# tek611r2.net
KiCad netlist of a schematic drawn in EAGLE
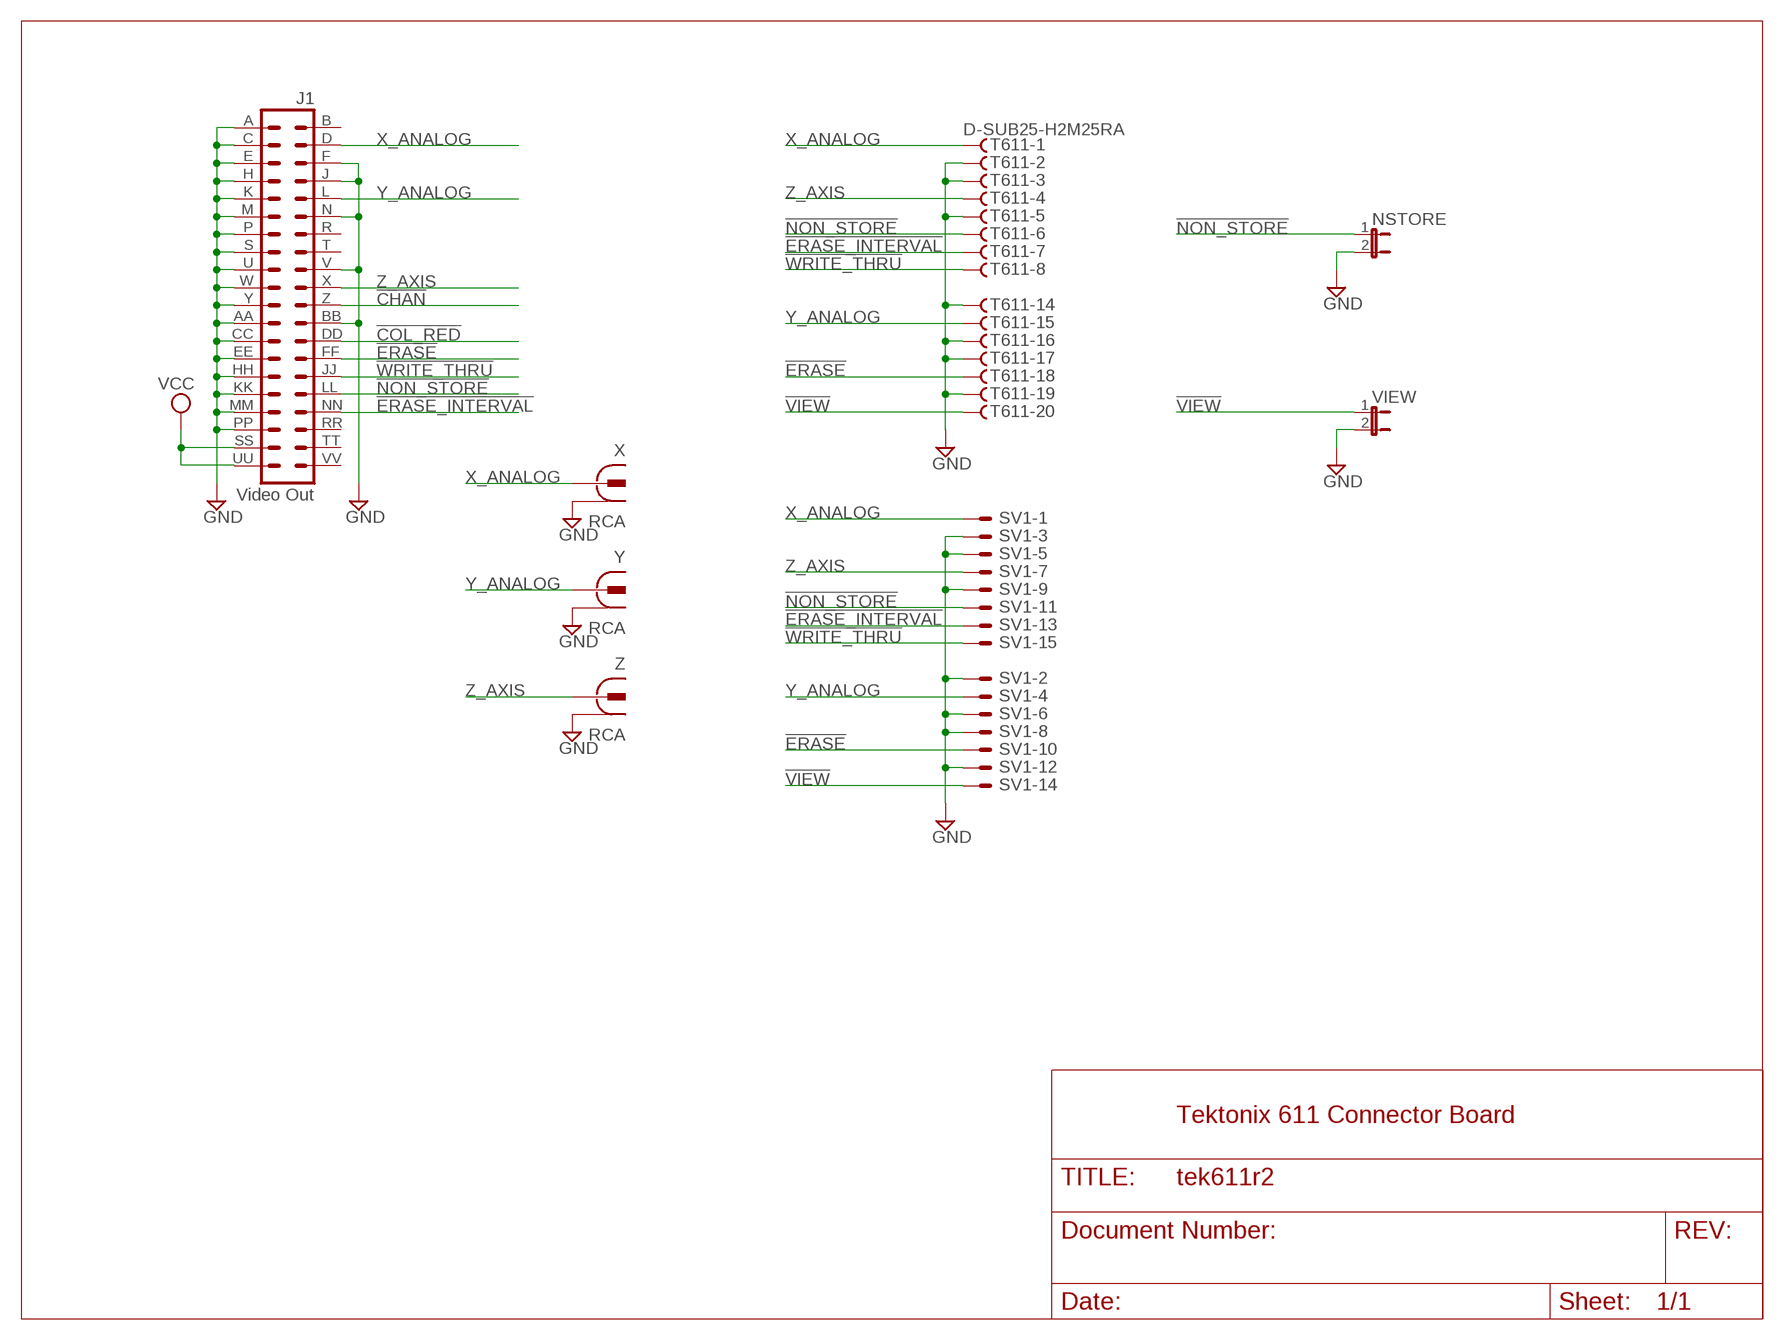
[diagram p0: schematic, sheet 1]

(export (version "E")
  (design (tool "Eeschema 10.0.6"))
  (components
    (comp (ref "J1")
      (value "Video Out")
      (footprint "eagle-import:DEC40PINH")
      (libsource (lib "eagle-import") (part "DEC40PINH"))
    )
    (comp (ref "NSTORE")
      (value "JP1E")
      (footprint "eagle-import:JP1")
      (libsource (lib "eagle-import") (part "JP1E"))
    )
    (comp (ref "SV1")
      (value "ML26LE")
      (footprint "eagle-import:ML26L")
      (libsource (lib "eagle-import") (part "ML26LE"))
    )
    (comp (ref "T611")
      (value "D-SUB25-H2M25RA")
      (footprint "eagle-import:H2M25RA")
      (libsource (lib "eagle-import") (part "D-SUB25-H2M25RA"))
    )
    (comp (ref "VIEW")
      (value "JP1E")
      (footprint "eagle-import:JP1")
      (libsource (lib "eagle-import") (part "JP1E"))
    )
    (comp (ref "X")
      (value "RCA")
      (footprint "eagle-import:RCA")
      (libsource (lib "eagle-import") (part "RCA"))
    )
    (comp (ref "Y")
      (value "RCA")
      (footprint "eagle-import:RCA")
      (libsource (lib "eagle-import") (part "RCA"))
    )
    (comp (ref "Z")
      (value "RCA")
      (footprint "eagle-import:RCA")
      (libsource (lib "eagle-import") (part "RCA"))
    )
  )
  (nets
    (net (code "1") (name "/X_ANALOG") (class "Default")
      (node (ref "J1") (pin "D") (pinfunction "4_D") (pintype "bidirectional"))
      (node (ref "SV1") (pin "1") (pinfunction "S_1") (pintype "passive"))
      (node (ref "T611") (pin "1") (pinfunction "F_1") (pintype "passive"))
      (node (ref "X") (pin "2") (pinfunction "2_2") (pintype "passive"))
    )
    (net (code "2") (name "/Y_ANALOG") (class "Default")
      (node (ref "J1") (pin "L") (pinfunction "10_L") (pintype "bidirectional"))
      (node (ref "SV1") (pin "4") (pinfunction "S_4") (pintype "passive"))
      (node (ref "T611") (pin "15") (pinfunction "F_15") (pintype "passive"))
      (node (ref "Y") (pin "2") (pinfunction "2_2") (pintype "passive"))
    )
    (net (code "3") (name "/Z_AXIS") (class "Default")
      (node (ref "J1") (pin "X") (pinfunction "20_X") (pintype "bidirectional"))
      (node (ref "SV1") (pin "7") (pinfunction "S_7") (pintype "passive"))
      (node (ref "T611") (pin "4") (pinfunction "F_4") (pintype "passive"))
      (node (ref "Z") (pin "2") (pinfunction "2_2") (pintype "passive"))
    )
    (net (code "4") (name "/~{CHAN}") (class "Default")
      (node (ref "J1") (pin "Z") (pinfunction "22_Z") (pintype "bidirectional"))
    )
    (net (code "5") (name "/~{COL_RED}") (class "Default")
      (node (ref "J1") (pin "DD") (pinfunction "26_DD") (pintype "bidirectional"))
    )
    (net (code "6") (name "/~{ERASE_INTERVAL}") (class "Default")
      (node (ref "J1") (pin "NN") (pinfunction "34_NN") (pintype "bidirectional"))
      (node (ref "SV1") (pin "13") (pinfunction "S_13") (pintype "passive"))
      (node (ref "T611") (pin "7") (pinfunction "F_7") (pintype "passive"))
    )
    (net (code "7") (name "/~{ERASE}") (class "Default")
      (node (ref "J1") (pin "FF") (pinfunction "28_FF") (pintype "bidirectional"))
      (node (ref "SV1") (pin "10") (pinfunction "S_10") (pintype "passive"))
      (node (ref "T611") (pin "18") (pinfunction "F_18") (pintype "passive"))
    )
    (net (code "8") (name "/~{NON_STORE}") (class "Default")
      (node (ref "J1") (pin "LL") (pinfunction "32_LL") (pintype "bidirectional"))
      (node (ref "NSTORE") (pin "1") (pinfunction "1_1") (pintype "passive"))
      (node (ref "SV1") (pin "11") (pinfunction "S_11") (pintype "passive"))
      (node (ref "T611") (pin "6") (pinfunction "F_6") (pintype "passive"))
    )
    (net (code "9") (name "/~{VIEW}") (class "Default")
      (node (ref "SV1") (pin "14") (pinfunction "S_14") (pintype "passive"))
      (node (ref "T611") (pin "20") (pinfunction "F_20") (pintype "passive"))
      (node (ref "VIEW") (pin "1") (pinfunction "1_1") (pintype "passive"))
    )
    (net (code "10") (name "/~{WRITE_THRU}") (class "Default")
      (node (ref "J1") (pin "JJ") (pinfunction "30_JJ") (pintype "bidirectional"))
      (node (ref "SV1") (pin "15") (pinfunction "S_15") (pintype "passive"))
      (node (ref "T611") (pin "8") (pinfunction "F_8") (pintype "passive"))
    )
    (net (code "11") (name "GND") (class "Default")
      (node (ref "J1") (pin "A") (pinfunction "1_A") (pintype "bidirectional"))
      (node (ref "J1") (pin "AA") (pinfunction "23_AA") (pintype "bidirectional"))
      (node (ref "J1") (pin "BB") (pinfunction "24_BB") (pintype "bidirectional"))
      (node (ref "J1") (pin "C") (pinfunction "3_C") (pintype "bidirectional"))
      (node (ref "J1") (pin "CC") (pinfunction "25_CC") (pintype "bidirectional"))
      (node (ref "J1") (pin "E") (pinfunction "5_E") (pintype "bidirectional"))
      (node (ref "J1") (pin "EE") (pinfunction "27_EE") (pintype "bidirectional"))
      (node (ref "J1") (pin "F") (pinfunction "6_F") (pintype "bidirectional"))
      (node (ref "J1") (pin "H") (pinfunction "7_H") (pintype "bidirectional"))
      (node (ref "J1") (pin "HH") (pinfunction "29_HH") (pintype "bidirectional"))
      (node (ref "J1") (pin "J") (pinfunction "8_J") (pintype "bidirectional"))
      (node (ref "J1") (pin "K") (pinfunction "9_K") (pintype "bidirectional"))
      (node (ref "J1") (pin "KK") (pinfunction "31_KK") (pintype "bidirectional"))
      (node (ref "J1") (pin "M") (pinfunction "11_M") (pintype "bidirectional"))
      (node (ref "J1") (pin "MM") (pinfunction "33_MM") (pintype "bidirectional"))
      (node (ref "J1") (pin "N") (pinfunction "12_N") (pintype "bidirectional"))
      (node (ref "J1") (pin "P") (pinfunction "13_P") (pintype "bidirectional"))
      (node (ref "J1") (pin "PP") (pinfunction "35_PP") (pintype "bidirectional"))
      (node (ref "J1") (pin "S") (pinfunction "15_S") (pintype "bidirectional"))
      (node (ref "J1") (pin "U") (pinfunction "17_U") (pintype "bidirectional"))
      (node (ref "J1") (pin "V") (pinfunction "18_V") (pintype "bidirectional"))
      (node (ref "J1") (pin "W") (pinfunction "19_W") (pintype "bidirectional"))
      (node (ref "J1") (pin "Y") (pinfunction "21_Y") (pintype "bidirectional"))
      (node (ref "NSTORE") (pin "2") (pinfunction "2_2") (pintype "passive"))
      (node (ref "SV1") (pin "12") (pinfunction "S_12") (pintype "passive"))
      (node (ref "SV1") (pin "2") (pinfunction "S_2") (pintype "passive"))
      (node (ref "SV1") (pin "3") (pinfunction "S_3") (pintype "passive"))
      (node (ref "SV1") (pin "5") (pinfunction "S_5") (pintype "passive"))
      (node (ref "SV1") (pin "6") (pinfunction "S_6") (pintype "passive"))
      (node (ref "SV1") (pin "8") (pinfunction "S_8") (pintype "passive"))
      (node (ref "SV1") (pin "9") (pinfunction "S_9") (pintype "passive"))
      (node (ref "T611") (pin "14") (pinfunction "F_14") (pintype "passive"))
      (node (ref "T611") (pin "16") (pinfunction "F_16") (pintype "passive"))
      (node (ref "T611") (pin "17") (pinfunction "F_17") (pintype "passive"))
      (node (ref "T611") (pin "19") (pinfunction "F_19") (pintype "passive"))
      (node (ref "T611") (pin "2") (pinfunction "F_2") (pintype "passive"))
      (node (ref "T611") (pin "3") (pinfunction "F_3") (pintype "passive"))
      (node (ref "T611") (pin "5") (pinfunction "F_5") (pintype "passive"))
      (node (ref "VIEW") (pin "2") (pinfunction "2_2") (pintype "passive"))
      (node (ref "X") (pin "1") (pinfunction "1_1") (pintype "passive"))
      (node (ref "X") (pin "1@1") (pinfunction "1_1@1") (pintype "passive"))
      (node (ref "X") (pin "1@2") (pinfunction "1_1@2") (pintype "passive"))
      (node (ref "Y") (pin "1") (pinfunction "1_1") (pintype "passive"))
      (node (ref "Y") (pin "1@1") (pinfunction "1_1@1") (pintype "passive"))
      (node (ref "Y") (pin "1@2") (pinfunction "1_1@2") (pintype "passive"))
      (node (ref "Z") (pin "1") (pinfunction "1_1") (pintype "passive"))
      (node (ref "Z") (pin "1@1") (pinfunction "1_1@1") (pintype "passive"))
      (node (ref "Z") (pin "1@2") (pinfunction "1_1@2") (pintype "passive"))
    )
    (net (code "12") (name "VCC") (class "Default")
      (node (ref "J1") (pin "SS") (pinfunction "37_SS") (pintype "bidirectional"))
      (node (ref "J1") (pin "UU") (pinfunction "39_UU") (pintype "bidirectional"))
    )
    (net (code "13") (name "unconnected-(J1-2-PadB)") (class "Default")
      (node (ref "J1") (pin "B") (pinfunction "2_B") (pintype "bidirectional"))
    )
    (net (code "14") (name "unconnected-(J1-14-PadR)") (class "Default")
      (node (ref "J1") (pin "R") (pinfunction "14_R") (pintype "bidirectional"))
    )
    (net (code "15") (name "unconnected-(J1-16-PadT)") (class "Default")
      (node (ref "J1") (pin "T") (pinfunction "16_T") (pintype "bidirectional"))
    )
    (net (code "16") (name "unconnected-(J1-36-PadRR)") (class "Default")
      (node (ref "J1") (pin "RR") (pinfunction "36_RR") (pintype "bidirectional"))
    )
    (net (code "17") (name "unconnected-(J1-38-PadTT)") (class "Default")
      (node (ref "J1") (pin "TT") (pinfunction "38_TT") (pintype "bidirectional"))
    )
    (net (code "18") (name "unconnected-(J1-40-PadVV)") (class "Default")
      (node (ref "J1") (pin "VV") (pinfunction "40_VV") (pintype "bidirectional"))
    )
  )
)
